# HallShield.net
KiCad netlist of a schematic drawn in EAGLE
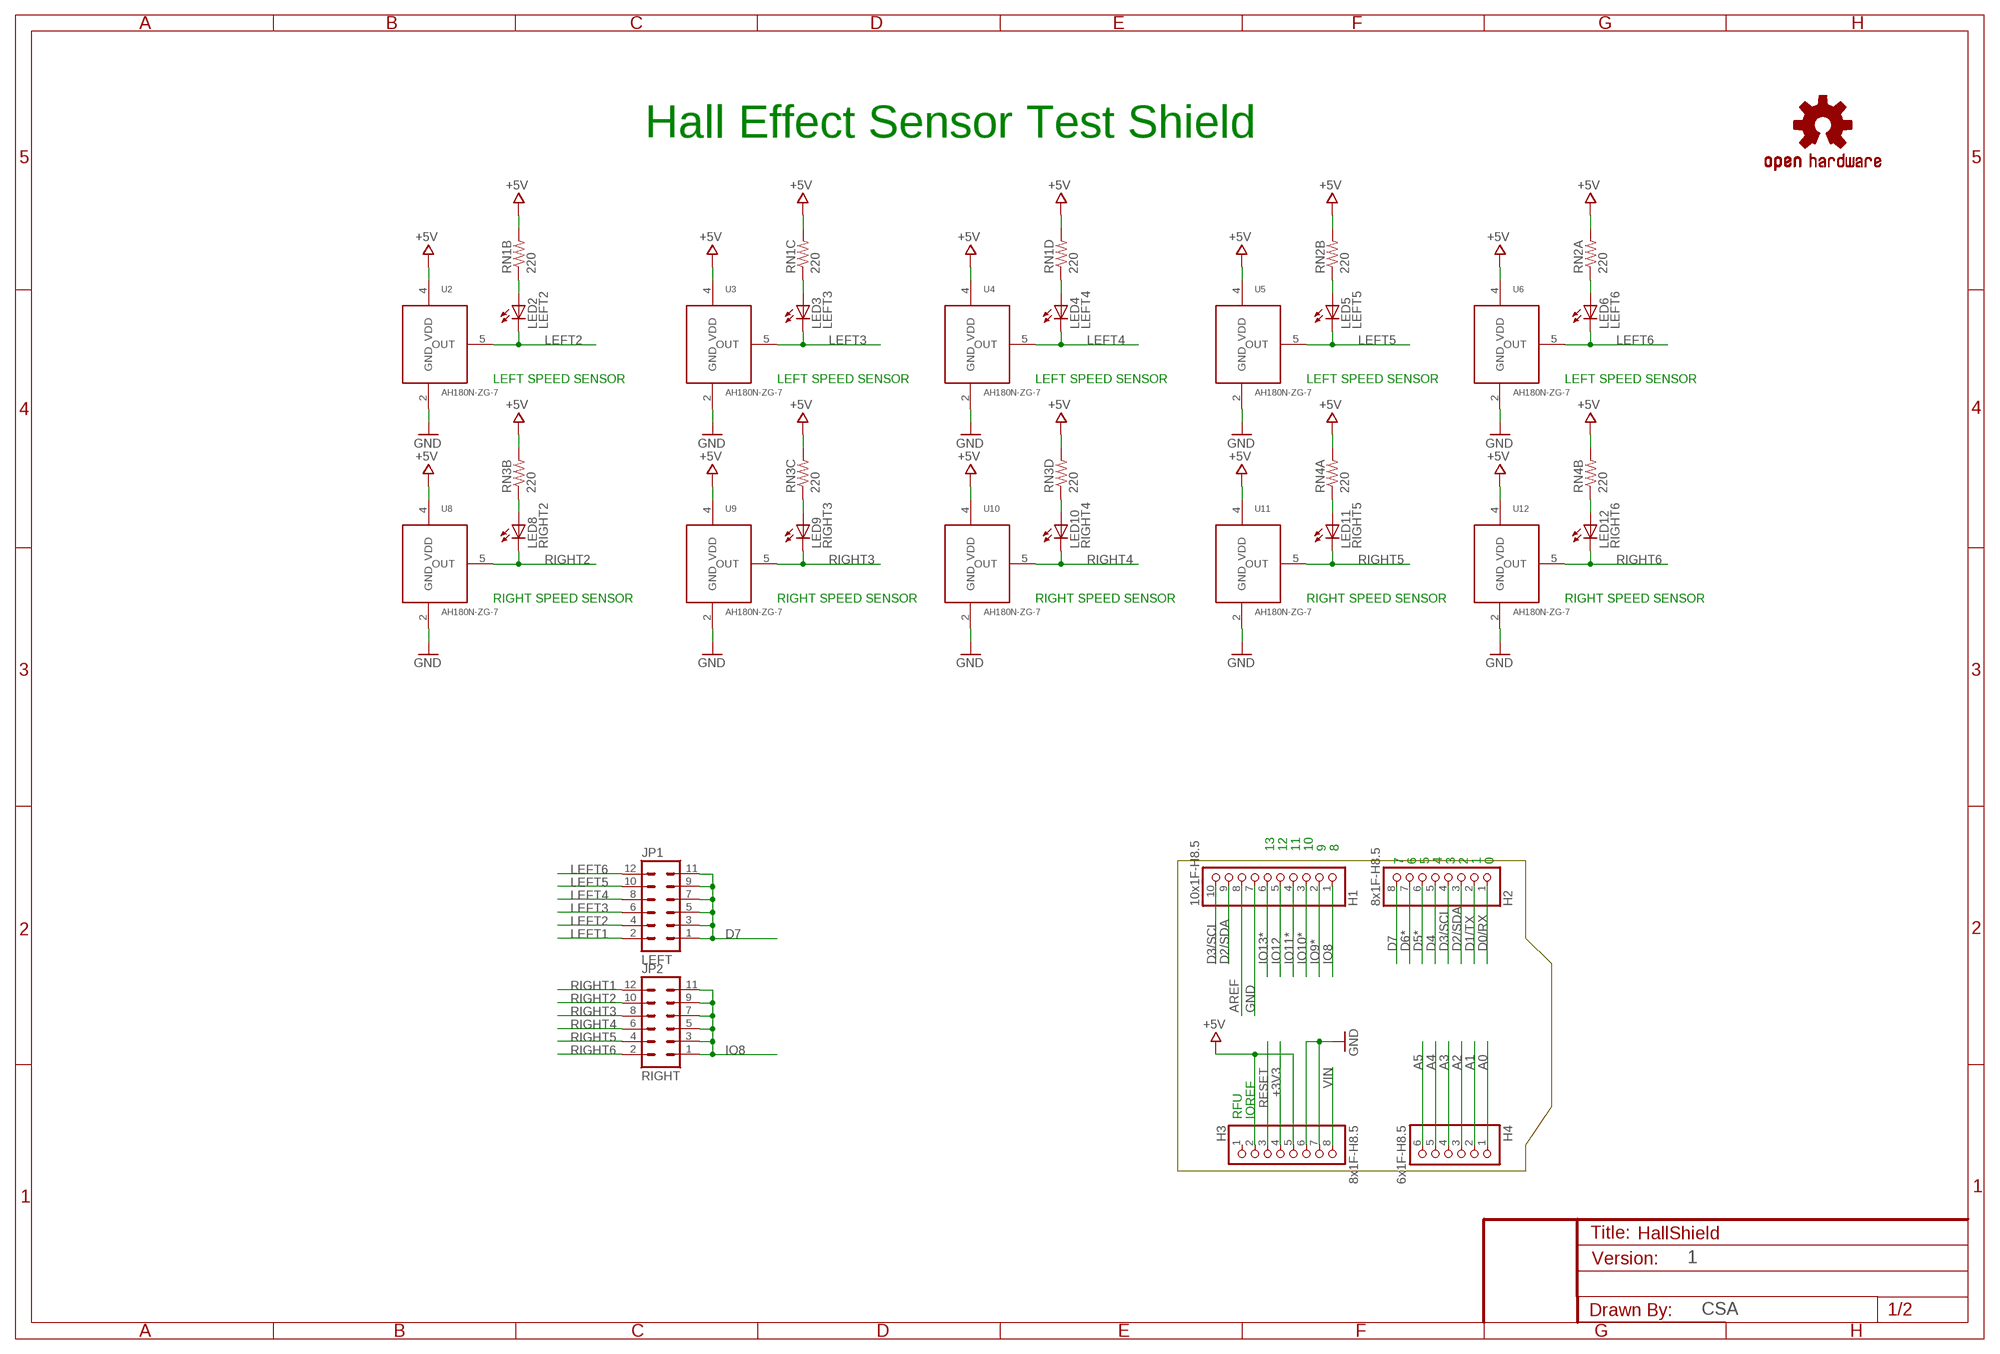
[diagram p0: schematic, sheet 1]
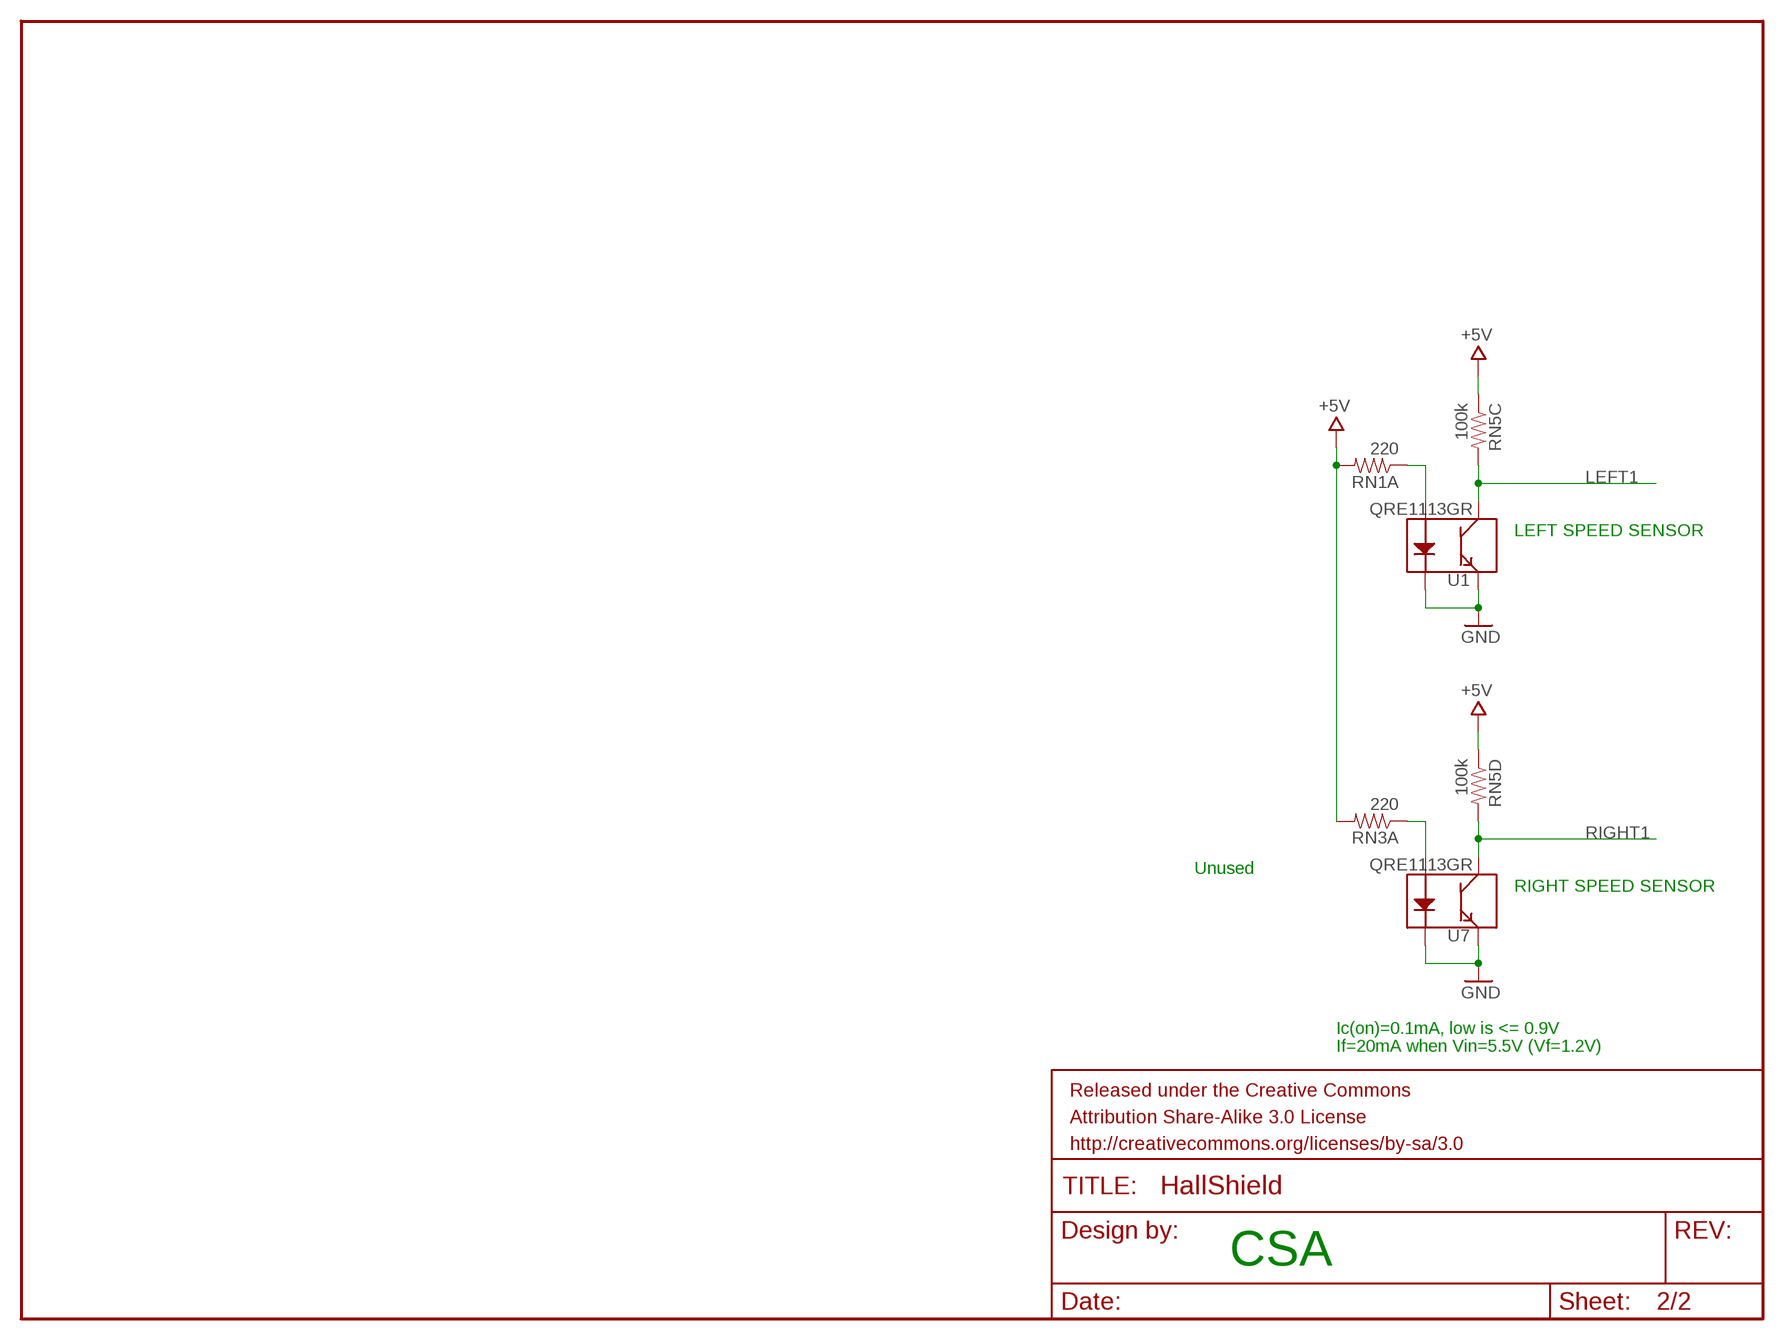
[diagram p1: schematic, sheet 2]

(export (version "E")
  (design (tool "Eeschema 10.0.6"))
  (components
    (comp (ref "H1")
      (value "10x1F-H8.5")
      (footprint "eagle-import:1X10")
      (libsource (lib "eagle-import") (part "PINHD-1X10"))
    )
    (comp (ref "H2")
      (value "8x1F-H8.5")
      (footprint "eagle-import:1X08")
      (libsource (lib "eagle-import") (part "PINHD-1X8"))
    )
    (comp (ref "H3")
      (value "8x1F-H8.5")
      (footprint "eagle-import:1X08")
      (libsource (lib "eagle-import") (part "PINHD-1X8"))
    )
    (comp (ref "H4")
      (value "6x1F-H8.5")
      (footprint "eagle-import:1X06")
      (libsource (lib "eagle-import") (part "PINHD-1X6"))
    )
    (comp (ref "JP1")
      (value "LEFT")
      (footprint "eagle-import:MA06-2")
      (libsource (lib "eagle-import") (part "MA06-2"))
    )
    (comp (ref "JP2")
      (value "RIGHT")
      (footprint "eagle-import:MA06-2")
      (libsource (lib "eagle-import") (part "MA06-2"))
    )
    (comp (ref "LED2")
      (value "LEFT2")
      (footprint "eagle-import:LED0805")
      (libsource (lib "eagle-import") (part "LED0805"))
    )
    (comp (ref "LED3")
      (value "LEFT3")
      (footprint "eagle-import:LED0805")
      (libsource (lib "eagle-import") (part "LED0805"))
    )
    (comp (ref "LED4")
      (value "LEFT4")
      (footprint "eagle-import:LED0805")
      (libsource (lib "eagle-import") (part "LED0805"))
    )
    (comp (ref "LED5")
      (value "LEFT5")
      (footprint "eagle-import:LED0805")
      (libsource (lib "eagle-import") (part "LED0805"))
    )
    (comp (ref "LED6")
      (value "LEFT6")
      (footprint "eagle-import:LED0805")
      (libsource (lib "eagle-import") (part "LED0805"))
    )
    (comp (ref "LED8")
      (value "RIGHT2")
      (footprint "eagle-import:LED0805")
      (libsource (lib "eagle-import") (part "LED0805"))
    )
    (comp (ref "LED9")
      (value "RIGHT3")
      (footprint "eagle-import:LED0805")
      (libsource (lib "eagle-import") (part "LED0805"))
    )
    (comp (ref "LED10")
      (value "RIGHT4")
      (footprint "eagle-import:LED0805")
      (libsource (lib "eagle-import") (part "LED0805"))
    )
    (comp (ref "LED11")
      (value "RIGHT5")
      (footprint "eagle-import:LED0805")
      (libsource (lib "eagle-import") (part "LED0805"))
    )
    (comp (ref "LED12")
      (value "RIGHT6")
      (footprint "eagle-import:LED0805")
      (libsource (lib "eagle-import") (part "LED0805"))
    )
    (comp (ref "RN1")
      (value "220")
      (footprint "eagle-import:CRA06S")
      (libsource (lib "eagle-import") (part "RESISTOR-ARRAYCRA06S"))
    )
    (comp (ref "RN2")
      (value "220")
      (footprint "eagle-import:CRA06S")
      (libsource (lib "eagle-import") (part "RESISTOR-ARRAYCRA06S"))
    )
    (comp (ref "RN3")
      (value "220")
      (footprint "eagle-import:CRA06S")
      (libsource (lib "eagle-import") (part "RESISTOR-ARRAYCRA06S"))
    )
    (comp (ref "RN4")
      (value "220")
      (footprint "eagle-import:CRA06S")
      (libsource (lib "eagle-import") (part "RESISTOR-ARRAYCRA06S"))
    )
    (comp (ref "U$5")
      (value "OSHW-LOGOL")
      (footprint "eagle-import:OSHW-LOGO-L")
      (libsource (lib "eagle-import") (part "OSHW-LOGOL"))
    )
    (comp (ref "U2")
      (value "AH180N-ZG-7")
      (footprint "eagle-import:SOT553")
      (libsource (lib "eagle-import") (part "AH180N-ZG-7"))
    )
    (comp (ref "U3")
      (value "AH180N-ZG-7")
      (footprint "eagle-import:SOT553")
      (libsource (lib "eagle-import") (part "AH180N-ZG-7"))
    )
    (comp (ref "U4")
      (value "AH180N-ZG-7")
      (footprint "eagle-import:SOT553")
      (libsource (lib "eagle-import") (part "AH180N-ZG-7"))
    )
    (comp (ref "U5")
      (value "AH180N-ZG-7")
      (footprint "eagle-import:SOT553")
      (libsource (lib "eagle-import") (part "AH180N-ZG-7"))
    )
    (comp (ref "U6")
      (value "AH180N-ZG-7")
      (footprint "eagle-import:SOT553")
      (libsource (lib "eagle-import") (part "AH180N-ZG-7"))
    )
    (comp (ref "U8")
      (value "AH180N-ZG-7")
      (footprint "eagle-import:SOT553")
      (libsource (lib "eagle-import") (part "AH180N-ZG-7"))
    )
    (comp (ref "U9")
      (value "AH180N-ZG-7")
      (footprint "eagle-import:SOT553")
      (libsource (lib "eagle-import") (part "AH180N-ZG-7"))
    )
    (comp (ref "U10")
      (value "AH180N-ZG-7")
      (footprint "eagle-import:SOT553")
      (libsource (lib "eagle-import") (part "AH180N-ZG-7"))
    )
    (comp (ref "U11")
      (value "AH180N-ZG-7")
      (footprint "eagle-import:SOT553")
      (libsource (lib "eagle-import") (part "AH180N-ZG-7"))
    )
    (comp (ref "U12")
      (value "AH180N-ZG-7")
      (footprint "eagle-import:SOT553")
      (libsource (lib "eagle-import") (part "AH180N-ZG-7"))
    )
    (comp (ref "RN5")
      (value "100k")
      (footprint "eagle-import:CRA06S")
      (libsource (lib "eagle-import") (part "RESISTOR-ARRAYCRA06S"))
    )
    (comp (ref "U1")
      (value "QRE1113GR")
      (footprint "eagle-import:QRE1113GR")
      (libsource (lib "eagle-import") (part "QRE1113GR"))
    )
    (comp (ref "U7")
      (value "QRE1113GR")
      (footprint "eagle-import:QRE1113GR")
      (libsource (lib "eagle-import") (part "QRE1113GR"))
    )
  )
  (nets
    (net (code "1") (name "+3V3") (class "Default")
      (node (ref "H3") (pin "4") (pinfunction "4_4") (pintype "passive"))
    )
    (net (code "2") (name "+5V") (class "Default")
      (node (ref "H3") (pin "2") (pinfunction "2_2") (pintype "passive"))
      (node (ref "H3") (pin "5") (pinfunction "5_5") (pintype "passive"))
      (node (ref "RN1") (pin "5") (pinfunction "2_5") (pintype "passive"))
      (node (ref "RN1") (pin "6") (pinfunction "2_6") (pintype "passive"))
      (node (ref "RN1") (pin "7") (pinfunction "2_7") (pintype "passive"))
      (node (ref "RN1") (pin "8") (pinfunction "2_8") (pintype "passive"))
      (node (ref "RN2") (pin "7") (pinfunction "2_7") (pintype "passive"))
      (node (ref "RN2") (pin "8") (pinfunction "2_8") (pintype "passive"))
      (node (ref "RN3") (pin "5") (pinfunction "2_5") (pintype "passive"))
      (node (ref "RN3") (pin "6") (pinfunction "2_6") (pintype "passive"))
      (node (ref "RN3") (pin "7") (pinfunction "2_7") (pintype "passive"))
      (node (ref "RN3") (pin "8") (pinfunction "2_8") (pintype "passive"))
      (node (ref "RN4") (pin "7") (pinfunction "2_7") (pintype "passive"))
      (node (ref "RN4") (pin "8") (pinfunction "2_8") (pintype "passive"))
      (node (ref "RN5") (pin "3") (pinfunction "1_3") (pintype "passive"))
      (node (ref "RN5") (pin "4") (pinfunction "1_4") (pintype "passive"))
      (node (ref "U10") (pin "4") (pinfunction "VDD_4") (pintype "passive"))
      (node (ref "U11") (pin "4") (pinfunction "VDD_4") (pintype "passive"))
      (node (ref "U12") (pin "4") (pinfunction "VDD_4") (pintype "passive"))
      (node (ref "U2") (pin "4") (pinfunction "VDD_4") (pintype "passive"))
      (node (ref "U3") (pin "4") (pinfunction "VDD_4") (pintype "passive"))
      (node (ref "U4") (pin "4") (pinfunction "VDD_4") (pintype "passive"))
      (node (ref "U5") (pin "4") (pinfunction "VDD_4") (pintype "passive"))
      (node (ref "U6") (pin "4") (pinfunction "VDD_4") (pintype "passive"))
      (node (ref "U8") (pin "4") (pinfunction "VDD_4") (pintype "passive"))
      (node (ref "U9") (pin "4") (pinfunction "VDD_4") (pintype "passive"))
    )
    (net (code "3") (name "A0") (class "Default")
      (node (ref "H4") (pin "1") (pinfunction "1_1") (pintype "passive"))
    )
    (net (code "4") (name "A1") (class "Default")
      (node (ref "H4") (pin "2") (pinfunction "2_2") (pintype "passive"))
    )
    (net (code "5") (name "A2") (class "Default")
      (node (ref "H4") (pin "3") (pinfunction "3_3") (pintype "passive"))
    )
    (net (code "6") (name "A3") (class "Default")
      (node (ref "H4") (pin "4") (pinfunction "4_4") (pintype "passive"))
    )
    (net (code "7") (name "A4") (class "Default")
      (node (ref "H4") (pin "5") (pinfunction "5_5") (pintype "passive"))
    )
    (net (code "8") (name "A5") (class "Default")
      (node (ref "H4") (pin "6") (pinfunction "6_6") (pintype "passive"))
    )
    (net (code "9") (name "AREF") (class "Default")
      (node (ref "H1") (pin "8") (pinfunction "8_8") (pintype "passive"))
    )
    (net (code "10") (name "D0{slash}RX") (class "Default")
      (node (ref "H2") (pin "1") (pinfunction "1_1") (pintype "passive"))
    )
    (net (code "11") (name "D1{slash}TX") (class "Default")
      (node (ref "H2") (pin "2") (pinfunction "2_2") (pintype "passive"))
    )
    (net (code "12") (name "D2{slash}SDA") (class "Default")
      (node (ref "H1") (pin "9") (pinfunction "9_9") (pintype "passive"))
      (node (ref "H2") (pin "3") (pinfunction "3_3") (pintype "passive"))
    )
    (net (code "13") (name "D3{slash}SCL") (class "Default")
      (node (ref "H1") (pin "10") (pinfunction "10_10") (pintype "passive"))
      (node (ref "H2") (pin "4") (pinfunction "4_4") (pintype "passive"))
    )
    (net (code "14") (name "D4") (class "Default")
      (node (ref "H2") (pin "5") (pinfunction "5_5") (pintype "passive"))
    )
    (net (code "15") (name "D5*") (class "Default")
      (node (ref "H2") (pin "6") (pinfunction "6_6") (pintype "passive"))
    )
    (net (code "16") (name "D6*") (class "Default")
      (node (ref "H2") (pin "7") (pinfunction "7_7") (pintype "passive"))
    )
    (net (code "17") (name "D7") (class "Default")
      (node (ref "H2") (pin "8") (pinfunction "8_8") (pintype "passive"))
      (node (ref "JP1") (pin "1") (pinfunction "1_1") (pintype "passive"))
      (node (ref "JP1") (pin "11") (pinfunction "11_11") (pintype "passive"))
      (node (ref "JP1") (pin "3") (pinfunction "3_3") (pintype "passive"))
      (node (ref "JP1") (pin "5") (pinfunction "5_5") (pintype "passive"))
      (node (ref "JP1") (pin "7") (pinfunction "7_7") (pintype "passive"))
      (node (ref "JP1") (pin "9") (pinfunction "9_9") (pintype "passive"))
    )
    (net (code "18") (name "GND") (class "Default")
      (node (ref "H1") (pin "7") (pinfunction "7_7") (pintype "passive"))
      (node (ref "H3") (pin "6") (pinfunction "6_6") (pintype "passive"))
      (node (ref "H3") (pin "7") (pinfunction "7_7") (pintype "passive"))
      (node (ref "U1") (pin "2") (pinfunction "K_2") (pintype "passive"))
      (node (ref "U1") (pin "4") (pinfunction "E_4") (pintype "passive"))
      (node (ref "U10") (pin "2") (pinfunction "GND_2") (pintype "passive"))
      (node (ref "U11") (pin "2") (pinfunction "GND_2") (pintype "passive"))
      (node (ref "U12") (pin "2") (pinfunction "GND_2") (pintype "passive"))
      (node (ref "U2") (pin "2") (pinfunction "GND_2") (pintype "passive"))
      (node (ref "U3") (pin "2") (pinfunction "GND_2") (pintype "passive"))
      (node (ref "U4") (pin "2") (pinfunction "GND_2") (pintype "passive"))
      (node (ref "U5") (pin "2") (pinfunction "GND_2") (pintype "passive"))
      (node (ref "U6") (pin "2") (pinfunction "GND_2") (pintype "passive"))
      (node (ref "U7") (pin "2") (pinfunction "K_2") (pintype "passive"))
      (node (ref "U7") (pin "4") (pinfunction "E_4") (pintype "passive"))
      (node (ref "U8") (pin "2") (pinfunction "GND_2") (pintype "passive"))
      (node (ref "U9") (pin "2") (pinfunction "GND_2") (pintype "passive"))
    )
    (net (code "19") (name "IO8") (class "Default")
      (node (ref "H1") (pin "1") (pinfunction "1_1") (pintype "passive"))
      (node (ref "JP2") (pin "1") (pinfunction "1_1") (pintype "passive"))
      (node (ref "JP2") (pin "11") (pinfunction "11_11") (pintype "passive"))
      (node (ref "JP2") (pin "3") (pinfunction "3_3") (pintype "passive"))
      (node (ref "JP2") (pin "5") (pinfunction "5_5") (pintype "passive"))
      (node (ref "JP2") (pin "7") (pinfunction "7_7") (pintype "passive"))
      (node (ref "JP2") (pin "9") (pinfunction "9_9") (pintype "passive"))
    )
    (net (code "20") (name "IO9*") (class "Default")
      (node (ref "H1") (pin "2") (pinfunction "2_2") (pintype "passive"))
    )
    (net (code "21") (name "IO10*") (class "Default")
      (node (ref "H1") (pin "3") (pinfunction "3_3") (pintype "passive"))
    )
    (net (code "22") (name "IO11*") (class "Default")
      (node (ref "H1") (pin "4") (pinfunction "4_4") (pintype "passive"))
    )
    (net (code "23") (name "IO12") (class "Default")
      (node (ref "H1") (pin "5") (pinfunction "5_5") (pintype "passive"))
    )
    (net (code "24") (name "IO13*") (class "Default")
      (node (ref "H1") (pin "6") (pinfunction "6_6") (pintype "passive"))
    )
    (net (code "25") (name "LEFT1") (class "Default")
      (node (ref "JP1") (pin "2") (pinfunction "2_2") (pintype "passive"))
      (node (ref "RN5") (pin "6") (pinfunction "2_6") (pintype "passive"))
      (node (ref "U1") (pin "3") (pinfunction "C_3") (pintype "passive"))
    )
    (net (code "26") (name "LEFT2") (class "Default")
      (node (ref "JP1") (pin "4") (pinfunction "4_4") (pintype "passive"))
      (node (ref "LED2") (pin "C") (pinfunction "C_C") (pintype "passive"))
      (node (ref "U2") (pin "5") (pinfunction "OUT_5") (pintype "open_collector"))
    )
    (net (code "27") (name "LEFT3") (class "Default")
      (node (ref "JP1") (pin "6") (pinfunction "6_6") (pintype "passive"))
      (node (ref "LED3") (pin "C") (pinfunction "C_C") (pintype "passive"))
      (node (ref "U3") (pin "5") (pinfunction "OUT_5") (pintype "open_collector"))
    )
    (net (code "28") (name "LEFT4") (class "Default")
      (node (ref "JP1") (pin "8") (pinfunction "8_8") (pintype "passive"))
      (node (ref "LED4") (pin "C") (pinfunction "C_C") (pintype "passive"))
      (node (ref "U4") (pin "5") (pinfunction "OUT_5") (pintype "open_collector"))
    )
    (net (code "29") (name "LEFT5") (class "Default")
      (node (ref "JP1") (pin "10") (pinfunction "10_10") (pintype "passive"))
      (node (ref "LED5") (pin "C") (pinfunction "C_C") (pintype "passive"))
      (node (ref "U5") (pin "5") (pinfunction "OUT_5") (pintype "open_collector"))
    )
    (net (code "30") (name "LEFT6") (class "Default")
      (node (ref "JP1") (pin "12") (pinfunction "12_12") (pintype "passive"))
      (node (ref "LED6") (pin "C") (pinfunction "C_C") (pintype "passive"))
      (node (ref "U6") (pin "5") (pinfunction "OUT_5") (pintype "open_collector"))
    )
    (net (code "31") (name "Net-(LED6-PadA)") (class "Default")
      (node (ref "LED6") (pin "A") (pinfunction "A_A") (pintype "passive"))
      (node (ref "RN2") (pin "1") (pinfunction "1_1") (pintype "passive"))
    )
    (net (code "32") (name "Net-(LED11-PadA)") (class "Default")
      (node (ref "LED11") (pin "A") (pinfunction "A_A") (pintype "passive"))
      (node (ref "RN4") (pin "1") (pinfunction "1_1") (pintype "passive"))
    )
    (net (code "33") (name "Net-(RN1B-1)") (class "Default")
      (node (ref "LED2") (pin "A") (pinfunction "A_A") (pintype "passive"))
      (node (ref "RN1") (pin "2") (pinfunction "1_2") (pintype "passive"))
    )
    (net (code "34") (name "Net-(RN1C-1)") (class "Default")
      (node (ref "LED3") (pin "A") (pinfunction "A_A") (pintype "passive"))
      (node (ref "RN1") (pin "3") (pinfunction "1_3") (pintype "passive"))
    )
    (net (code "35") (name "Net-(RN1D-1)") (class "Default")
      (node (ref "LED4") (pin "A") (pinfunction "A_A") (pintype "passive"))
      (node (ref "RN1") (pin "4") (pinfunction "1_4") (pintype "passive"))
    )
    (net (code "36") (name "Net-(RN2B-1)") (class "Default")
      (node (ref "LED5") (pin "A") (pinfunction "A_A") (pintype "passive"))
      (node (ref "RN2") (pin "2") (pinfunction "1_2") (pintype "passive"))
    )
    (net (code "37") (name "Net-(RN3B-1)") (class "Default")
      (node (ref "LED8") (pin "A") (pinfunction "A_A") (pintype "passive"))
      (node (ref "RN3") (pin "2") (pinfunction "1_2") (pintype "passive"))
    )
    (net (code "38") (name "Net-(RN3C-1)") (class "Default")
      (node (ref "LED9") (pin "A") (pinfunction "A_A") (pintype "passive"))
      (node (ref "RN3") (pin "3") (pinfunction "1_3") (pintype "passive"))
    )
    (net (code "39") (name "Net-(RN3D-1)") (class "Default")
      (node (ref "LED10") (pin "A") (pinfunction "A_A") (pintype "passive"))
      (node (ref "RN3") (pin "4") (pinfunction "1_4") (pintype "passive"))
    )
    (net (code "40") (name "Net-(RN4B-1)") (class "Default")
      (node (ref "LED12") (pin "A") (pinfunction "A_A") (pintype "passive"))
      (node (ref "RN4") (pin "2") (pinfunction "1_2") (pintype "passive"))
    )
    (net (code "41") (name "Net-(U1-A)") (class "Default")
      (node (ref "RN1") (pin "1") (pinfunction "1_1") (pintype "passive"))
      (node (ref "U1") (pin "1") (pinfunction "A_1") (pintype "passive"))
    )
    (net (code "42") (name "Net-(U7-A)") (class "Default")
      (node (ref "RN3") (pin "1") (pinfunction "1_1") (pintype "passive"))
      (node (ref "U7") (pin "1") (pinfunction "A_1") (pintype "passive"))
    )
    (net (code "43") (name "RESET") (class "Default")
      (node (ref "H3") (pin "3") (pinfunction "3_3") (pintype "passive"))
    )
    (net (code "44") (name "RIGHT1") (class "Default")
      (node (ref "JP2") (pin "12") (pinfunction "12_12") (pintype "passive"))
      (node (ref "RN5") (pin "5") (pinfunction "2_5") (pintype "passive"))
      (node (ref "U7") (pin "3") (pinfunction "C_3") (pintype "passive"))
    )
    (net (code "45") (name "RIGHT2") (class "Default")
      (node (ref "JP2") (pin "10") (pinfunction "10_10") (pintype "passive"))
      (node (ref "LED8") (pin "C") (pinfunction "C_C") (pintype "passive"))
      (node (ref "U8") (pin "5") (pinfunction "OUT_5") (pintype "open_collector"))
    )
    (net (code "46") (name "RIGHT3") (class "Default")
      (node (ref "JP2") (pin "8") (pinfunction "8_8") (pintype "passive"))
      (node (ref "LED9") (pin "C") (pinfunction "C_C") (pintype "passive"))
      (node (ref "U9") (pin "5") (pinfunction "OUT_5") (pintype "open_collector"))
    )
    (net (code "47") (name "RIGHT4") (class "Default")
      (node (ref "JP2") (pin "6") (pinfunction "6_6") (pintype "passive"))
      (node (ref "LED10") (pin "C") (pinfunction "C_C") (pintype "passive"))
      (node (ref "U10") (pin "5") (pinfunction "OUT_5") (pintype "open_collector"))
    )
    (net (code "48") (name "RIGHT5") (class "Default")
      (node (ref "JP2") (pin "4") (pinfunction "4_4") (pintype "passive"))
      (node (ref "LED11") (pin "C") (pinfunction "C_C") (pintype "passive"))
      (node (ref "U11") (pin "5") (pinfunction "OUT_5") (pintype "open_collector"))
    )
    (net (code "49") (name "RIGHT6") (class "Default")
      (node (ref "JP2") (pin "2") (pinfunction "2_2") (pintype "passive"))
      (node (ref "LED12") (pin "C") (pinfunction "C_C") (pintype "passive"))
      (node (ref "U12") (pin "5") (pinfunction "OUT_5") (pintype "open_collector"))
    )
    (net (code "50") (name "VIN") (class "Default")
      (node (ref "H3") (pin "8") (pinfunction "8_8") (pintype "passive"))
    )
    (net (code "51") (name "unconnected-(H3-Pad1)") (class "Default")
      (node (ref "H3") (pin "1") (pinfunction "1_1") (pintype "passive"))
    )
  )
)
